# connectors.net
KiCad netlist of a schematic drawn in Altium Designer
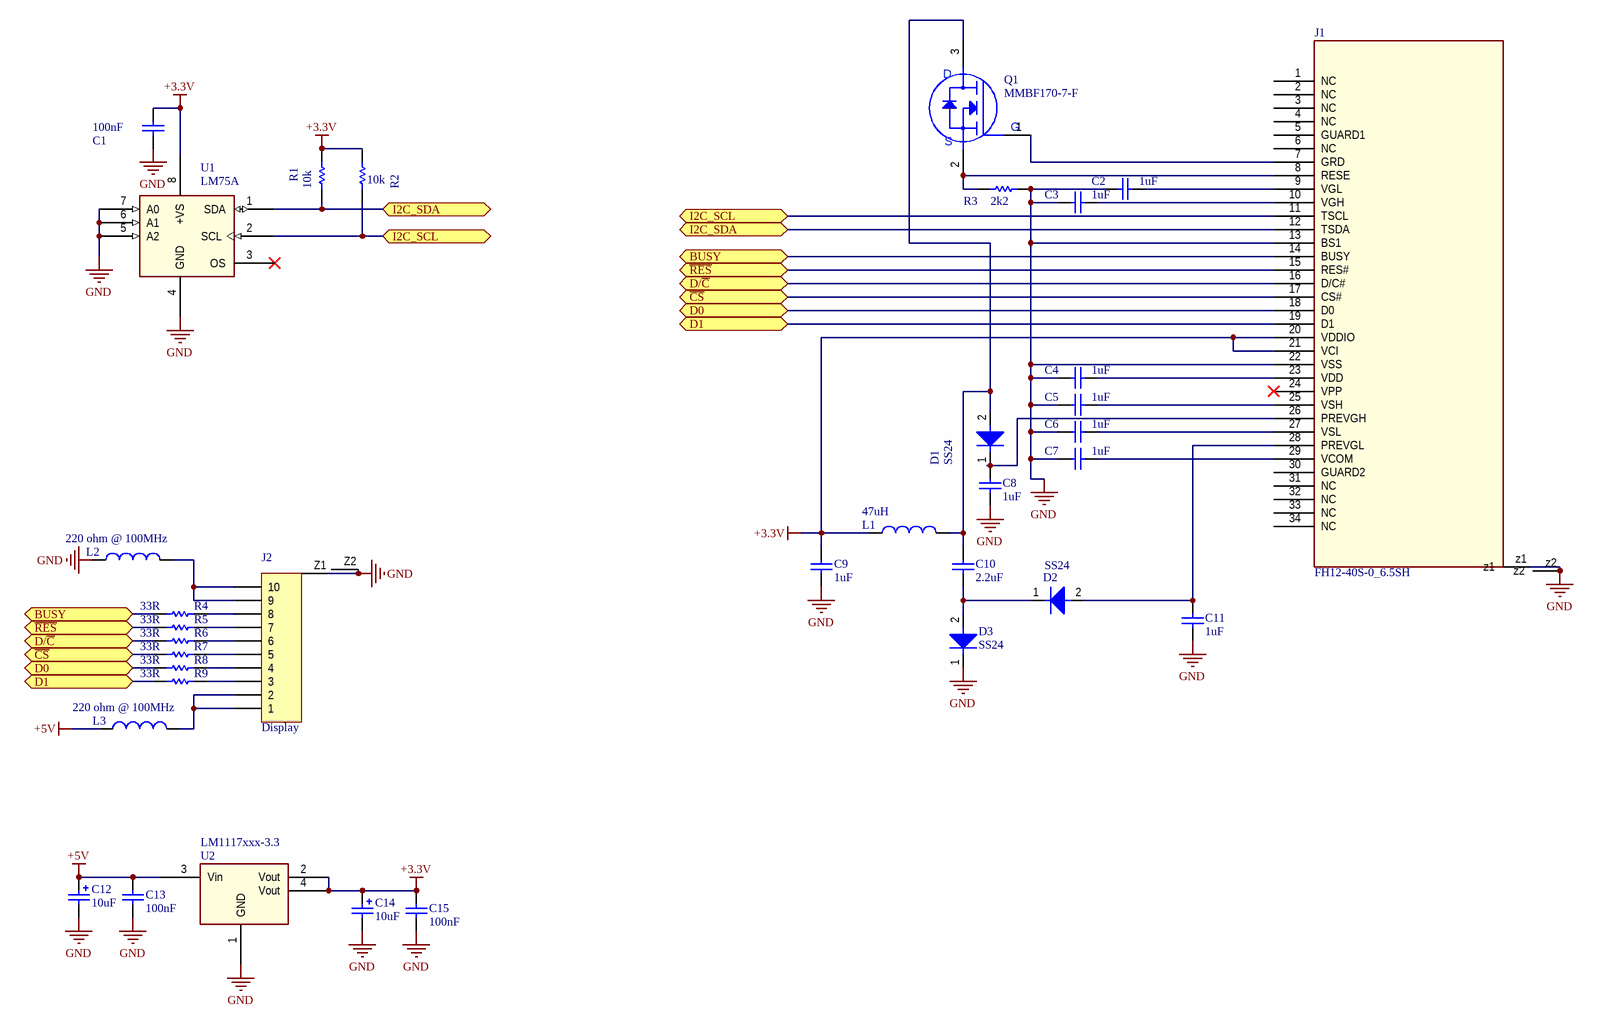
[diagram p0: connectors.SchDoc]

(export (version "E")
  (design (tool "Eeschema 10.0.6"))
  (components
    (comp (ref "C1")
      (value "100nF")
      (footprint "0603_[1608]")
      (description "Ceramic X7R 50V")
      (fields (field (name "PUBLISHER") "Altium Limited"))
      (libsource (lib "DEVELER_Library") (part "Cap"))
    )
    (comp (ref "C2")
      (value "1uF")
      (footprint "0603_[1608]")
      (description "Ceraminc 25V")
      (fields (field (name "PUBLISHER") "Altium Limited"))
      (libsource (lib "develer_library") (part "Cap"))
    )
    (comp (ref "C3")
      (value "1uF")
      (footprint "0603_[1608]")
      (description "Ceraminc 25V")
      (fields (field (name "PUBLISHER") "Altium Limited"))
      (libsource (lib "develer_library") (part "Cap"))
    )
    (comp (ref "C4")
      (value "1uF")
      (footprint "0603_[1608]")
      (description "Ceraminc 25V")
      (fields (field (name "PUBLISHER") "Altium Limited"))
      (libsource (lib "develer_library") (part "Cap"))
    )
    (comp (ref "C5")
      (value "1uF")
      (footprint "0603_[1608]")
      (description "Ceraminc 25V")
      (fields (field (name "PUBLISHER") "Altium Limited"))
      (libsource (lib "develer_library") (part "Cap"))
    )
    (comp (ref "C6")
      (value "1uF")
      (footprint "0603_[1608]")
      (description "Ceraminc 25V")
      (fields (field (name "PUBLISHER") "Altium Limited"))
      (libsource (lib "develer_library") (part "Cap"))
    )
    (comp (ref "C7")
      (value "1uF")
      (footprint "0603_[1608]")
      (description "Ceraminc 25V")
      (fields (field (name "PUBLISHER") "Altium Limited"))
      (libsource (lib "develer_library") (part "Cap"))
    )
    (comp (ref "C8")
      (value "1uF")
      (footprint "0603_[1608]")
      (description "Ceraminc 25V")
      (fields (field (name "PUBLISHER") "Altium Limited"))
      (libsource (lib "develer_library") (part "Cap"))
    )
    (comp (ref "C9")
      (value "1uF")
      (footprint "0603_[1608]")
      (description "Ceraminc 25V")
      (fields (field (name "PUBLISHER") "Altium Limited"))
      (libsource (lib "develer_library") (part "Cap"))
    )
    (comp (ref "C10")
      (value "2.2uF")
      (footprint "0603_[1608]")
      (description "Ceraminc 25V")
      (fields (field (name "PUBLISHER") "Altium Limited"))
      (libsource (lib "develer_library") (part "Cap"))
    )
    (comp (ref "C11")
      (value "1uF")
      (footprint "0603_[1608]")
      (description "Ceraminc 25V")
      (fields (field (name "PUBLISHER") "Altium Limited"))
      (libsource (lib "develer_library") (part "Cap"))
    )
    (comp (ref "C12")
      (value "10uF")
      (footprint "1206_[3216]")
      (description "Ceramic X5R 25V")
      (fields (field (name "PUBLISHER") "Altium Limited"))
      (libsource (lib "DEVELER_Library") (part "Cap Pol1"))
    )
    (comp (ref "C13")
      (value "100nF")
      (footprint "0603_[1608]")
      (description "Ceramic X7R 50V")
      (fields (field (name "PUBLISHER") "Altium Limited"))
      (libsource (lib "") (part "Cap_1"))
    )
    (comp (ref "C14")
      (value "10uF")
      (footprint "1206_[3216]")
      (description "Ceramic X5R 25V")
      (fields (field (name "PUBLISHER") "Altium Limited"))
      (libsource (lib "DEVELER_Library") (part "Cap Pol1"))
    )
    (comp (ref "C15")
      (value "100nF")
      (footprint "0603_[1608]")
      (description "Ceramic X7R 50V")
      (fields (field (name "PUBLISHER") "Altium Limited"))
      (libsource (lib "") (part "Cap_1"))
    )
    (comp (ref "D1")
      (value "SS24")
      (footprint "DO214AA_12")
      (description "Schottky diode Vf as lower as possible, 0.2 to 0.4V and the repetitive peak reverse voltage > 25V.")
      (libsource (lib "DEVELER_Library") (part "Diode"))
    )
    (comp (ref "D2")
      (value "SS24")
      (footprint "DO214AA_12")
      (description "Schottky diode Vf as lower as possible, 0.2 to 0.4V and the repetitive peak reverse voltage > 25V.")
      (libsource (lib "DEVELER_Library") (part "Diode"))
    )
    (comp (ref "D3")
      (value "SS24")
      (footprint "DO214AA_12")
      (description "Schottky diode Vf as lower as possible, 0.2 to 0.4V and the repetitive peak reverse voltage > 25V.")
      (libsource (lib "DEVELER_Library") (part "Diode"))
    )
    (comp (ref "J1")
      (value "FH12-40S-0_6.5SH")
      (footprint "fcp_zif_34pin_0,5mm")
      (description "FH34SRJ-34S-0.5SH(50)")
      (libsource (lib "EPD EXTENSION BOARD GEN2 20160215_Library") (part "FH12-40S-0_6.5SH"))
    )
    (comp (ref "J2")
      (value "Display")
      (footprint "fcc-zif_10pin_0.5mm")
      (description "Header, 10-Pin")
      (fields (field (name "PUBLISHER") "Altium Limited"))
      (libsource (lib "Miscellaneous Connectors") (part "Header 10"))
    )
    (comp (ref "L1")
      (value "47uH")
      (footprint "0805_[2012]")
      (description "0.8A")
      (libsource (lib "DEVELER_Library") (part "Inductor"))
    )
    (comp (ref "L2")
      (value "220 ohm @ 100MHz")
      (footprint "0805_[2012]")
      (description "WE 742792022")
      (libsource (lib "DEVELER_Library") (part "Inductor"))
    )
    (comp (ref "L3")
      (value "220 ohm @ 100MHz")
      (footprint "0805_[2012]")
      (description "WE 742792022")
      (libsource (lib "DEVELER_Library") (part "Inductor"))
    )
    (comp (ref "Q1")
      (value "MMBF170-7-F")
      (footprint "sot-23")
      (description "VDSS=30V, VGS-th<2.5V@250uA.")
      (libsource (lib "develer_library") (part "MOSFET-N 3pin"))
    )
    (comp (ref "R1")
      (value "10k")
      (footprint "0603_[1608]")
      (description "Resistor")
      (libsource (lib "DEVELER_Library") (part "Res1"))
    )
    (comp (ref "R2")
      (value "10k")
      (footprint "0603_[1608]")
      (description "Resistor")
      (libsource (lib "DEVELER_Library") (part "Res1"))
    )
    (comp (ref "R3")
      (value "2k2")
      (footprint "0603_[1608]")
      (description "Resistor")
      (fields (field (name "PUBLISHER") "Altium Limited"))
      (libsource (lib "develer_library") (part "Res1"))
    )
    (comp (ref "R4")
      (value "33R")
      (footprint "0603_[1608]")
      (description "Resistor")
      (fields (field (name "PUBLISHER") "Altium Limited"))
      (libsource (lib "simboli") (part "Res1"))
    )
    (comp (ref "R5")
      (value "33R")
      (footprint "0603_[1608]")
      (description "Resistor")
      (fields (field (name "PUBLISHER") "Altium Limited"))
      (libsource (lib "simboli") (part "Res1"))
    )
    (comp (ref "R6")
      (value "33R")
      (footprint "0603_[1608]")
      (description "Resistor")
      (fields (field (name "PUBLISHER") "Altium Limited"))
      (libsource (lib "simboli") (part "Res1"))
    )
    (comp (ref "R7")
      (value "33R")
      (footprint "0603_[1608]")
      (description "Resistor")
      (fields (field (name "PUBLISHER") "Altium Limited"))
      (libsource (lib "simboli") (part "Res1"))
    )
    (comp (ref "R8")
      (value "33R")
      (footprint "0603_[1608]")
      (description "Resistor")
      (fields (field (name "PUBLISHER") "Altium Limited"))
      (libsource (lib "simboli") (part "Res1"))
    )
    (comp (ref "R9")
      (value "33R")
      (footprint "0603_[1608]")
      (description "Resistor")
      (fields (field (name "PUBLISHER") "Altium Limited"))
      (libsource (lib "simboli") (part "Res1"))
    )
    (comp (ref "U1")
      (value "LM75A")
      (footprint "SOIC8")
      (description "Temperature sensor")
      (libsource (lib "DEVELER_Library") (part "LM75"))
    )
    (comp (ref "U2")
      (value "LM1117xxx-3.3")
      (footprint "SOT-223")
      (description "LM1117 LDO Fixed output")
      (libsource (lib "develer_library") (part "LM1117-FIXED-OUT"))
    )
  )
  (nets
    (net (code "1") (name "+3.3V") (class "Default")
      (node (ref "C1") (pin "2") (pinfunction "2_2") (pintype "passive"))
      (node (ref "C14") (pin "1") (pinfunction "1_1") (pintype "passive"))
      (node (ref "C15") (pin "2") (pinfunction "2_2") (pintype "passive"))
      (node (ref "C9") (pin "2") (pinfunction "2_2") (pintype "passive"))
      (node (ref "J1") (pin "20") (pinfunction "VDDIO_20") (pintype "passive"))
      (node (ref "J1") (pin "21") (pinfunction "VCI_21") (pintype "passive"))
      (node (ref "L1") (pin "1") (pinfunction "1_1") (pintype "passive"))
      (node (ref "R1") (pin "1") (pinfunction "1_1") (pintype "passive"))
      (node (ref "R2") (pin "1") (pinfunction "1_1") (pintype "passive"))
      (node (ref "U1") (pin "8") (pinfunction "+VS_8") (pintype "power_in"))
      (node (ref "U2") (pin "2") (pinfunction "Vout_2") (pintype "passive"))
      (node (ref "U2") (pin "4") (pinfunction "Vout_4") (pintype "passive"))
    )
    (net (code "2") (name "+5V") (class "Default")
      (node (ref "C12") (pin "1") (pinfunction "1_1") (pintype "passive"))
      (node (ref "C13") (pin "2") (pinfunction "2_2") (pintype "passive"))
      (node (ref "L3") (pin "1") (pinfunction "1_1") (pintype "passive"))
      (node (ref "U2") (pin "3") (pinfunction "Vin_3") (pintype "passive"))
    )
    (net (code "3") (name "/BUSY") (class "Default")
      (node (ref "J1") (pin "14") (pinfunction "BUSY_14") (pintype "passive"))
      (node (ref "R4") (pin "2") (pinfunction "2_2") (pintype "passive"))
    )
    (net (code "4") (name "/D0") (class "Default")
      (node (ref "J1") (pin "18") (pinfunction "D0_18") (pintype "passive"))
      (node (ref "R8") (pin "2") (pinfunction "2_2") (pintype "passive"))
    )
    (net (code "5") (name "/D1") (class "Default")
      (node (ref "J1") (pin "19") (pinfunction "D1_19") (pintype "passive"))
      (node (ref "R9") (pin "2") (pinfunction "2_2") (pintype "passive"))
    )
    (net (code "6") (name "/D{slash}~{C}") (class "Default")
      (node (ref "J1") (pin "16") (pinfunction "D/C#_16") (pintype "passive"))
      (node (ref "R6") (pin "2") (pinfunction "2_2") (pintype "passive"))
    )
    (net (code "7") (name "/I2C_SCL") (class "Default")
      (node (ref "J1") (pin "11") (pinfunction "TSCL_11") (pintype "passive"))
      (node (ref "R2") (pin "2") (pinfunction "2_2") (pintype "passive"))
      (node (ref "U1") (pin "2") (pinfunction "SCL_2") (pintype "input"))
    )
    (net (code "8") (name "/I2C_SDA") (class "Default")
      (node (ref "J1") (pin "12") (pinfunction "TSDA_12") (pintype "passive"))
      (node (ref "R1") (pin "2") (pinfunction "2_2") (pintype "passive"))
      (node (ref "U1") (pin "1") (pinfunction "SDA_1") (pintype "bidirectional"))
    )
    (net (code "9") (name "/~{CS}") (class "Default")
      (node (ref "J1") (pin "17") (pinfunction "CS#_17") (pintype "passive"))
      (node (ref "R7") (pin "2") (pinfunction "2_2") (pintype "passive"))
    )
    (net (code "10") (name "/~{RES}") (class "Default")
      (node (ref "J1") (pin "15") (pinfunction "RES#_15") (pintype "passive"))
      (node (ref "R5") (pin "2") (pinfunction "2_2") (pintype "passive"))
    )
    (net (code "11") (name "GND") (class "Default")
      (node (ref "C1") (pin "1") (pinfunction "1_1") (pintype "passive"))
      (node (ref "C11") (pin "1") (pinfunction "1_1") (pintype "passive"))
      (node (ref "C12") (pin "2") (pinfunction "2_2") (pintype "passive"))
      (node (ref "C13") (pin "1") (pinfunction "1_1") (pintype "passive"))
      (node (ref "C14") (pin "2") (pinfunction "2_2") (pintype "passive"))
      (node (ref "C15") (pin "1") (pinfunction "1_1") (pintype "passive"))
      (node (ref "C2") (pin "1") (pinfunction "1_1") (pintype "passive"))
      (node (ref "C3") (pin "1") (pinfunction "1_1") (pintype "passive"))
      (node (ref "C4") (pin "1") (pinfunction "1_1") (pintype "passive"))
      (node (ref "C5") (pin "1") (pinfunction "1_1") (pintype "passive"))
      (node (ref "C6") (pin "1") (pinfunction "1_1") (pintype "passive"))
      (node (ref "C7") (pin "1") (pinfunction "1_1") (pintype "passive"))
      (node (ref "C8") (pin "1") (pinfunction "1_1") (pintype "passive"))
      (node (ref "C9") (pin "1") (pinfunction "1_1") (pintype "passive"))
      (node (ref "D3") (pin "1") (pinfunction "K_1") (pintype "passive"))
      (node (ref "J1") (pin "13") (pinfunction "BS1_13") (pintype "passive"))
      (node (ref "J1") (pin "22") (pinfunction "VSS_22") (pintype "passive"))
      (node (ref "J1") (pin "z1") (pinfunction "z1_z1") (pintype "passive"))
      (node (ref "J1") (pin "z2") (pinfunction "z2_z2") (pintype "passive"))
      (node (ref "J2") (pin "Z1") (pinfunction "Z1_Z1") (pintype "passive"))
      (node (ref "J2") (pin "Z2") (pinfunction "Z2_Z2") (pintype "passive"))
      (node (ref "L2") (pin "1") (pinfunction "1_1") (pintype "passive"))
      (node (ref "R3") (pin "1") (pinfunction "1_1") (pintype "passive"))
      (node (ref "U1") (pin "4") (pinfunction "GND_4") (pintype "power_in"))
      (node (ref "U1") (pin "5") (pinfunction "A2_5") (pintype "input"))
      (node (ref "U1") (pin "6") (pinfunction "A1_6") (pintype "input"))
      (node (ref "U1") (pin "7") (pinfunction "A0_7") (pintype "input"))
      (node (ref "U2") (pin "1") (pinfunction "GND_1") (pintype "passive"))
    )
    (net (code "12") (name "Net-(D1-A)") (class "Default")
      (node (ref "C10") (pin "2") (pinfunction "2_2") (pintype "passive"))
      (node (ref "D1") (pin "2") (pinfunction "A_2") (pintype "passive"))
      (node (ref "L1") (pin "2") (pinfunction "2_2") (pintype "passive"))
      (node (ref "Q1") (pin "3") (pinfunction "D_3") (pintype "passive"))
    )
    (net (code "13") (name "Net-(D1-K)") (class "Default")
      (node (ref "C8") (pin "2") (pinfunction "2_2") (pintype "passive"))
      (node (ref "D1") (pin "1") (pinfunction "K_1") (pintype "passive"))
      (node (ref "J1") (pin "26") (pinfunction "PREVGH_26") (pintype "passive"))
    )
    (net (code "14") (name "Net-(D2-A)") (class "Default")
      (node (ref "C11") (pin "2") (pinfunction "2_2") (pintype "passive"))
      (node (ref "D2") (pin "2") (pinfunction "A_2") (pintype "passive"))
      (node (ref "J1") (pin "28") (pinfunction "PREVGL_28") (pintype "passive"))
    )
    (net (code "15") (name "Net-(D2-K)") (class "Default")
      (node (ref "C10") (pin "1") (pinfunction "1_1") (pintype "passive"))
      (node (ref "D2") (pin "1") (pinfunction "K_1") (pintype "passive"))
      (node (ref "D3") (pin "2") (pinfunction "A_2") (pintype "passive"))
    )
    (net (code "16") (name "Net-(J1-GRD)") (class "Default")
      (node (ref "J1") (pin "7") (pinfunction "GRD_7") (pintype "passive"))
      (node (ref "Q1") (pin "1") (pinfunction "G_1") (pintype "passive"))
    )
    (net (code "17") (name "Net-(J1-RESE)") (class "Default")
      (node (ref "J1") (pin "8") (pinfunction "RESE_8") (pintype "passive"))
      (node (ref "Q1") (pin "2") (pinfunction "S_2") (pintype "passive"))
      (node (ref "R3") (pin "2") (pinfunction "2_2") (pintype "passive"))
    )
    (net (code "18") (name "Net-(J1-VCOM)") (class "Default")
      (node (ref "C7") (pin "2") (pinfunction "2_2") (pintype "passive"))
      (node (ref "J1") (pin "29") (pinfunction "VCOM_29") (pintype "passive"))
    )
    (net (code "19") (name "Net-(J1-VDD)") (class "Default")
      (node (ref "C4") (pin "2") (pinfunction "2_2") (pintype "passive"))
      (node (ref "J1") (pin "23") (pinfunction "VDD_23") (pintype "passive"))
    )
    (net (code "20") (name "Net-(J1-VGH)") (class "Default")
      (node (ref "C3") (pin "2") (pinfunction "2_2") (pintype "passive"))
      (node (ref "J1") (pin "10") (pinfunction "VGH_10") (pintype "passive"))
    )
    (net (code "21") (name "Net-(J1-VGL)") (class "Default")
      (node (ref "C2") (pin "2") (pinfunction "2_2") (pintype "passive"))
      (node (ref "J1") (pin "9") (pinfunction "VGL_9") (pintype "passive"))
    )
    (net (code "22") (name "Net-(J1-VSH)") (class "Default")
      (node (ref "C5") (pin "2") (pinfunction "2_2") (pintype "passive"))
      (node (ref "J1") (pin "25") (pinfunction "VSH_25") (pintype "passive"))
    )
    (net (code "23") (name "Net-(J1-VSL)") (class "Default")
      (node (ref "C6") (pin "2") (pinfunction "2_2") (pintype "passive"))
      (node (ref "J1") (pin "27") (pinfunction "VSL_27") (pintype "passive"))
    )
    (net (code "24") (name "Net-(J2-Pad1)") (class "Default")
      (node (ref "J2") (pin "1") (pinfunction "1_1") (pintype "passive"))
      (node (ref "J2") (pin "2") (pinfunction "2_2") (pintype "passive"))
      (node (ref "L3") (pin "2") (pinfunction "2_2") (pintype "passive"))
    )
    (net (code "25") (name "Net-(J2-Pad3)") (class "Default")
      (node (ref "J2") (pin "3") (pinfunction "3_3") (pintype "passive"))
      (node (ref "R9") (pin "1") (pinfunction "1_1") (pintype "passive"))
    )
    (net (code "26") (name "Net-(J2-Pad4)") (class "Default")
      (node (ref "J2") (pin "4") (pinfunction "4_4") (pintype "passive"))
      (node (ref "R8") (pin "1") (pinfunction "1_1") (pintype "passive"))
    )
    (net (code "27") (name "Net-(J2-Pad5)") (class "Default")
      (node (ref "J2") (pin "5") (pinfunction "5_5") (pintype "passive"))
      (node (ref "R7") (pin "1") (pinfunction "1_1") (pintype "passive"))
    )
    (net (code "28") (name "Net-(J2-Pad6)") (class "Default")
      (node (ref "J2") (pin "6") (pinfunction "6_6") (pintype "passive"))
      (node (ref "R6") (pin "1") (pinfunction "1_1") (pintype "passive"))
    )
    (net (code "29") (name "Net-(J2-Pad7)") (class "Default")
      (node (ref "J2") (pin "7") (pinfunction "7_7") (pintype "passive"))
      (node (ref "R5") (pin "1") (pinfunction "1_1") (pintype "passive"))
    )
    (net (code "30") (name "Net-(J2-Pad8)") (class "Default")
      (node (ref "J2") (pin "8") (pinfunction "8_8") (pintype "passive"))
      (node (ref "R4") (pin "1") (pinfunction "1_1") (pintype "passive"))
    )
    (net (code "31") (name "Net-(J2-Pad10)") (class "Default")
      (node (ref "J2") (pin "10") (pinfunction "10_10") (pintype "passive"))
      (node (ref "J2") (pin "9") (pinfunction "9_9") (pintype "passive"))
      (node (ref "L2") (pin "2") (pinfunction "2_2") (pintype "passive"))
    )
    (net (code "32") (name "unconnected-(J1-GUARD1-Pad5)") (class "Default")
      (node (ref "J1") (pin "5") (pinfunction "GUARD1_5") (pintype "passive"))
    )
    (net (code "33") (name "unconnected-(J1-GUARD2-Pad30)") (class "Default")
      (node (ref "J1") (pin "30") (pinfunction "GUARD2_30") (pintype "passive"))
    )
    (net (code "34") (name "unconnected-(J1-NC-Pad1)") (class "Default")
      (node (ref "J1") (pin "1") (pinfunction "NC_1") (pintype "passive"))
    )
    (net (code "35") (name "unconnected-(J1-NC-Pad2)") (class "Default")
      (node (ref "J1") (pin "2") (pinfunction "NC_2") (pintype "passive"))
    )
    (net (code "36") (name "unconnected-(J1-NC-Pad3)") (class "Default")
      (node (ref "J1") (pin "3") (pinfunction "NC_3") (pintype "passive"))
    )
    (net (code "37") (name "unconnected-(J1-NC-Pad4)") (class "Default")
      (node (ref "J1") (pin "4") (pinfunction "NC_4") (pintype "passive"))
    )
    (net (code "38") (name "unconnected-(J1-NC-Pad6)") (class "Default")
      (node (ref "J1") (pin "6") (pinfunction "NC_6") (pintype "passive"))
    )
    (net (code "39") (name "unconnected-(J1-NC-Pad31)") (class "Default")
      (node (ref "J1") (pin "31") (pinfunction "NC_31") (pintype "passive"))
    )
    (net (code "40") (name "unconnected-(J1-NC-Pad32)") (class "Default")
      (node (ref "J1") (pin "32") (pinfunction "NC_32") (pintype "passive"))
    )
    (net (code "41") (name "unconnected-(J1-NC-Pad33)") (class "Default")
      (node (ref "J1") (pin "33") (pinfunction "NC_33") (pintype "passive"))
    )
    (net (code "42") (name "unconnected-(J1-NC-Pad34)") (class "Default")
      (node (ref "J1") (pin "34") (pinfunction "NC_34") (pintype "passive"))
    )
    (net (code "43") (name "unconnected-(J1-VPP-Pad24)") (class "Default")
      (node (ref "J1") (pin "24") (pinfunction "VPP_24") (pintype "passive+no_connect"))
    )
    (net (code "44") (name "unconnected-(U1-OS-Pad3)") (class "Default")
      (node (ref "U1") (pin "3") (pinfunction "OS_3") (pintype "open_collector+no_connect"))
    )
  )
)
